# atf22_breakout.net
KiCad netlist of a schematic drawn in EAGLE
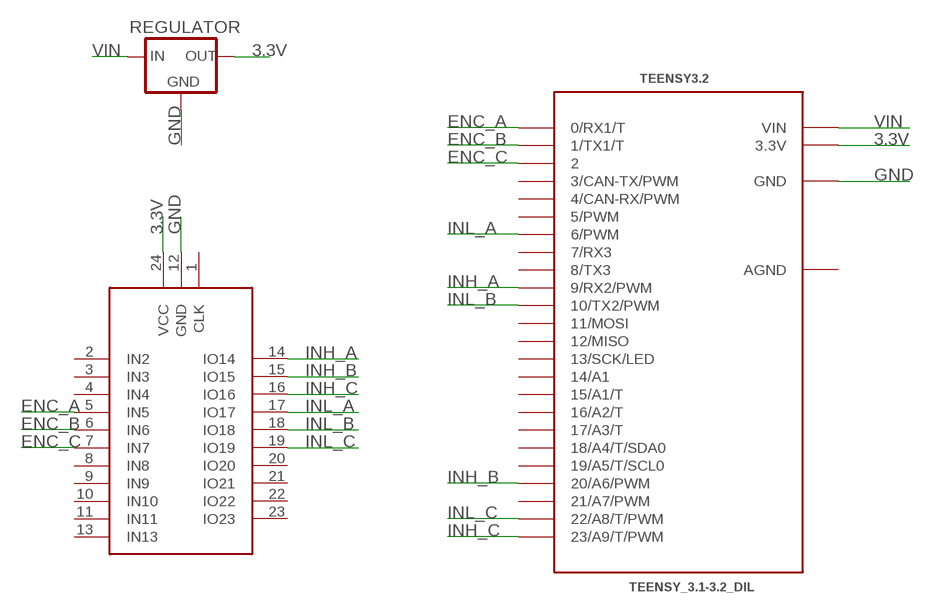
[diagram p0: schematic, sheet 1]

(export (version "E")
  (design (tool "Eeschema 10.0.6"))
  (components
    (comp (ref "ATF22")
      (value "ATF22")
      (footprint "eagle-import:PDIP-T24")
      (libsource (lib "eagle-import") (part "ATF22"))
    )
    (comp (ref "REGULATOR")
      (value "V_REG_78XXR-78E")
      (footprint "eagle-import:V78W")
      (libsource (lib "eagle-import") (part "V_REG_78XXR-78E"))
    )
    (comp (ref "TEENSY3.2")
      (value "TEENSY_3.1-3.2_DIL")
      (footprint "eagle-import:TEENSY_3.0-3.2&LC_DIL")
      (libsource (lib "eagle-import") (part "TEENSY_3.1-3.2_DIL"))
    )
  )
  (nets
    (net (code "1") (name "/3.3V") (class "Default")
      (node (ref "ATF22") (pin "24") (pinfunction "VCC_24") (pintype "bidirectional"))
      (node (ref "REGULATOR") (pin "OUT") (pinfunction "OUT_OUT") (pintype "output"))
      (node (ref "TEENSY3.2") (pin "3.3V") (pinfunction "3.3V_3.3V") (pintype "power_in"))
    )
    (net (code "2") (name "/AGND") (class "Default")
      (node (ref "TEENSY3.2") (pin "AGND") (pinfunction "AGND_AGND") (pintype "power_in"))
    )
    (net (code "3") (name "/ENC_A") (class "Default")
      (node (ref "ATF22") (pin "5") (pinfunction "IN5_5") (pintype "bidirectional"))
      (node (ref "TEENSY3.2") (pin "0") (pinfunction "0/RX1/T_0") (pintype "bidirectional"))
    )
    (net (code "4") (name "/ENC_B") (class "Default")
      (node (ref "ATF22") (pin "6") (pinfunction "IN6_6") (pintype "bidirectional"))
      (node (ref "TEENSY3.2") (pin "1") (pinfunction "1/TX1/T_1") (pintype "bidirectional"))
    )
    (net (code "5") (name "/ENC_C") (class "Default")
      (node (ref "ATF22") (pin "7") (pinfunction "IN7_7") (pintype "bidirectional"))
      (node (ref "TEENSY3.2") (pin "2") (pinfunction "2_2") (pintype "bidirectional"))
    )
    (net (code "6") (name "/GND") (class "Default")
      (node (ref "ATF22") (pin "12") (pinfunction "GND_12") (pintype "bidirectional"))
      (node (ref "REGULATOR") (pin "GND") (pinfunction "GND_GND") (pintype "input"))
      (node (ref "TEENSY3.2") (pin "GND") (pinfunction "GND_GND") (pintype "power_in"))
    )
    (net (code "7") (name "/INH_A") (class "Default")
      (node (ref "ATF22") (pin "14") (pinfunction "IO14_14") (pintype "bidirectional"))
      (node (ref "TEENSY3.2") (pin "9") (pinfunction "9/RX2/PWM_9") (pintype "bidirectional"))
    )
    (net (code "8") (name "/INH_B") (class "Default")
      (node (ref "ATF22") (pin "15") (pinfunction "IO15_15") (pintype "bidirectional"))
      (node (ref "TEENSY3.2") (pin "20/A6") (pinfunction "20/A6/PWM_20/A6") (pintype "bidirectional"))
    )
    (net (code "9") (name "/INH_C") (class "Default")
      (node (ref "ATF22") (pin "16") (pinfunction "IO16_16") (pintype "bidirectional"))
      (node (ref "TEENSY3.2") (pin "23/A9") (pinfunction "23/A9/T/PWM_23/A9") (pintype "bidirectional"))
    )
    (net (code "10") (name "/INL_A") (class "Default")
      (node (ref "ATF22") (pin "17") (pinfunction "IO17_17") (pintype "bidirectional"))
      (node (ref "TEENSY3.2") (pin "6") (pinfunction "6/PWM_6") (pintype "bidirectional"))
    )
    (net (code "11") (name "/INL_B") (class "Default")
      (node (ref "ATF22") (pin "18") (pinfunction "IO18_18") (pintype "bidirectional"))
      (node (ref "TEENSY3.2") (pin "10") (pinfunction "10/TX2/PWM_10") (pintype "bidirectional"))
    )
    (net (code "12") (name "/INL_C") (class "Default")
      (node (ref "ATF22") (pin "19") (pinfunction "IO19_19") (pintype "bidirectional"))
      (node (ref "TEENSY3.2") (pin "22/A8") (pinfunction "22/A8/T/PWM_22/A8") (pintype "bidirectional"))
    )
    (net (code "13") (name "/VIN") (class "Default")
      (node (ref "REGULATOR") (pin "IN") (pinfunction "IN_IN") (pintype "input"))
      (node (ref "TEENSY3.2") (pin "VIN") (pinfunction "VIN_VIN") (pintype "power_in"))
    )
    (net (code "14") (name "unconnected-(ATF22-CLK-Pad1)") (class "Default")
      (node (ref "ATF22") (pin "1") (pinfunction "CLK_1") (pintype "bidirectional"))
    )
    (net (code "15") (name "unconnected-(ATF22-IN2-Pad2)") (class "Default")
      (node (ref "ATF22") (pin "2") (pinfunction "IN2_2") (pintype "bidirectional"))
    )
    (net (code "16") (name "unconnected-(ATF22-IN3-Pad3)") (class "Default")
      (node (ref "ATF22") (pin "3") (pinfunction "IN3_3") (pintype "bidirectional"))
    )
    (net (code "17") (name "unconnected-(ATF22-IN4-Pad4)") (class "Default")
      (node (ref "ATF22") (pin "4") (pinfunction "IN4_4") (pintype "bidirectional"))
    )
    (net (code "18") (name "unconnected-(ATF22-IN8-Pad8)") (class "Default")
      (node (ref "ATF22") (pin "8") (pinfunction "IN8_8") (pintype "bidirectional"))
    )
    (net (code "19") (name "unconnected-(ATF22-IN9-Pad9)") (class "Default")
      (node (ref "ATF22") (pin "9") (pinfunction "IN9_9") (pintype "bidirectional"))
    )
    (net (code "20") (name "unconnected-(ATF22-IN10-Pad10)") (class "Default")
      (node (ref "ATF22") (pin "10") (pinfunction "IN10_10") (pintype "bidirectional"))
    )
    (net (code "21") (name "unconnected-(ATF22-IN11-Pad11)") (class "Default")
      (node (ref "ATF22") (pin "11") (pinfunction "IN11_11") (pintype "bidirectional"))
    )
    (net (code "22") (name "unconnected-(ATF22-IN13-Pad13)") (class "Default")
      (node (ref "ATF22") (pin "13") (pinfunction "IN13_13") (pintype "bidirectional"))
    )
    (net (code "23") (name "unconnected-(ATF22-IO20-Pad20)") (class "Default")
      (node (ref "ATF22") (pin "20") (pinfunction "IO20_20") (pintype "bidirectional"))
    )
    (net (code "24") (name "unconnected-(ATF22-IO21-Pad21)") (class "Default")
      (node (ref "ATF22") (pin "21") (pinfunction "IO21_21") (pintype "bidirectional"))
    )
    (net (code "25") (name "unconnected-(ATF22-IO22-Pad22)") (class "Default")
      (node (ref "ATF22") (pin "22") (pinfunction "IO22_22") (pintype "bidirectional"))
    )
    (net (code "26") (name "unconnected-(ATF22-IO23-Pad23)") (class "Default")
      (node (ref "ATF22") (pin "23") (pinfunction "IO23_23") (pintype "bidirectional"))
    )
    (net (code "27") (name "unconnected-(TEENSY3.2-3{slash}CAN-TX{slash}PWM-Pad3)") (class "Default")
      (node (ref "TEENSY3.2") (pin "3") (pinfunction "3/CAN-TX/PWM_3") (pintype "bidirectional"))
    )
    (net (code "28") (name "unconnected-(TEENSY3.2-4{slash}CAN-RX{slash}PWM-Pad4)") (class "Default")
      (node (ref "TEENSY3.2") (pin "4") (pinfunction "4/CAN-RX/PWM_4") (pintype "bidirectional"))
    )
    (net (code "29") (name "unconnected-(TEENSY3.2-5{slash}PWM-Pad5)") (class "Default")
      (node (ref "TEENSY3.2") (pin "5") (pinfunction "5/PWM_5") (pintype "bidirectional"))
    )
    (net (code "30") (name "unconnected-(TEENSY3.2-7{slash}RX3-Pad7)") (class "Default")
      (node (ref "TEENSY3.2") (pin "7") (pinfunction "7/RX3_7") (pintype "bidirectional"))
    )
    (net (code "31") (name "unconnected-(TEENSY3.2-8{slash}TX3-Pad8)") (class "Default")
      (node (ref "TEENSY3.2") (pin "8") (pinfunction "8/TX3_8") (pintype "bidirectional"))
    )
    (net (code "32") (name "unconnected-(TEENSY3.2-11{slash}MOSI-Pad11)") (class "Default")
      (node (ref "TEENSY3.2") (pin "11") (pinfunction "11/MOSI_11") (pintype "bidirectional"))
    )
    (net (code "33") (name "unconnected-(TEENSY3.2-12{slash}MISO-Pad12)") (class "Default")
      (node (ref "TEENSY3.2") (pin "12") (pinfunction "12/MISO_12") (pintype "bidirectional"))
    )
    (net (code "34") (name "unconnected-(TEENSY3.2-13{slash}SCK{slash}LED-Pad13)") (class "Default")
      (node (ref "TEENSY3.2") (pin "13") (pinfunction "13/SCK/LED_13") (pintype "bidirectional"))
    )
    (net (code "35") (name "unconnected-(TEENSY3.2-14{slash}A1-Pad14{slash}A0)") (class "Default")
      (node (ref "TEENSY3.2") (pin "14/A0") (pinfunction "14/A1_14/A0") (pintype "bidirectional"))
    )
    (net (code "36") (name "unconnected-(TEENSY3.2-15{slash}A1{slash}T-Pad15{slash}A1)") (class "Default")
      (node (ref "TEENSY3.2") (pin "15/A1") (pinfunction "15/A1/T_15/A1") (pintype "bidirectional"))
    )
    (net (code "37") (name "unconnected-(TEENSY3.2-16{slash}A2{slash}T-Pad16{slash}A2)") (class "Default")
      (node (ref "TEENSY3.2") (pin "16/A2") (pinfunction "16/A2/T_16/A2") (pintype "bidirectional"))
    )
    (net (code "38") (name "unconnected-(TEENSY3.2-17{slash}A3{slash}T-Pad17{slash}A3)") (class "Default")
      (node (ref "TEENSY3.2") (pin "17/A3") (pinfunction "17/A3/T_17/A3") (pintype "bidirectional"))
    )
    (net (code "39") (name "unconnected-(TEENSY3.2-18{slash}A4{slash}T{slash}SDA0-Pad18{slash}A4)") (class "Default")
      (node (ref "TEENSY3.2") (pin "18/A4") (pinfunction "18/A4/T/SDA0_18/A4") (pintype "bidirectional"))
    )
    (net (code "40") (name "unconnected-(TEENSY3.2-19{slash}A5{slash}T{slash}SCL0-Pad19{slash}A5)") (class "Default")
      (node (ref "TEENSY3.2") (pin "19/A5") (pinfunction "19/A5/T/SCL0_19/A5") (pintype "bidirectional"))
    )
    (net (code "41") (name "unconnected-(TEENSY3.2-21{slash}A7{slash}PWM-Pad21{slash}A7)") (class "Default")
      (node (ref "TEENSY3.2") (pin "21/A7") (pinfunction "21/A7/PWM_21/A7") (pintype "bidirectional"))
    )
  )
)
